# pqc-rev2.net
KiCad netlist of a schematic drawn in EAGLE
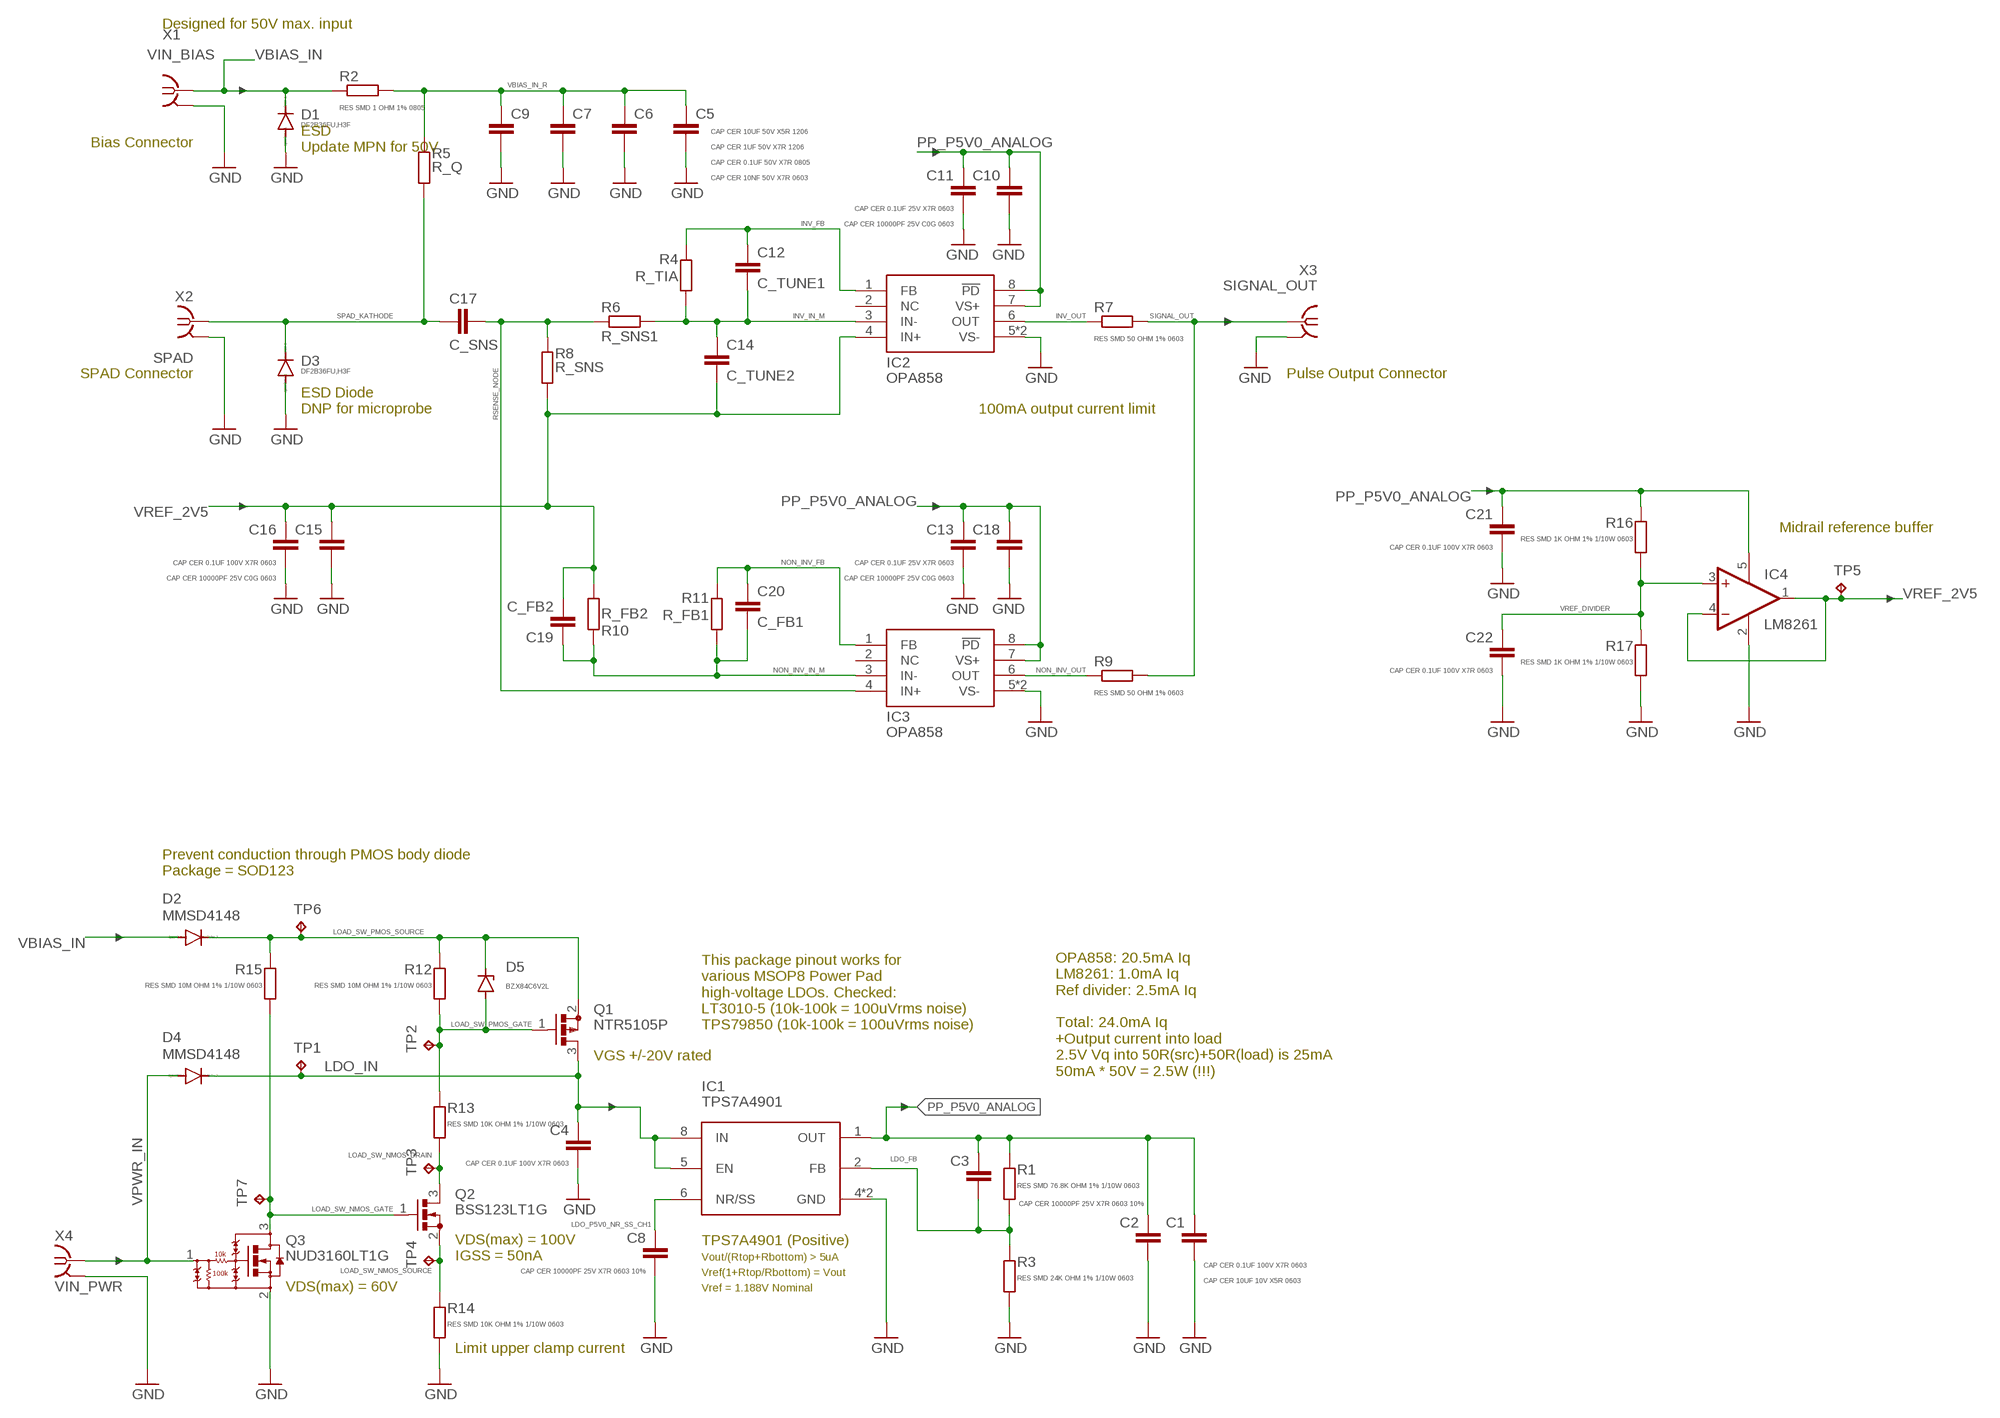
[diagram p0: schematic, sheet 1]

(export (version "E")
  (design (tool "Eeschema 10.0.6"))
  (components
    (comp (ref "C1")
      (value "CAP CER 10UF 10V X5R 0603")
      (footprint "eagle-import:C0603")
      (libsource (lib "eagle-import") (part "rcl-modified-footprints_C-EUC0603"))
    )
    (comp (ref "C2")
      (value "CAP CER 0.1UF 100V X7R 0603")
      (footprint "eagle-import:C0603")
      (libsource (lib "eagle-import") (part "rcl-modified-footprints_C-EUC0603"))
    )
    (comp (ref "C3")
      (value "CAP CER 10000PF 25V X7R 0603 10%")
      (footprint "eagle-import:C0603")
      (libsource (lib "eagle-import") (part "rcl-modified-footprints_C-EUC0603"))
    )
    (comp (ref "C4")
      (value "CAP CER 0.1UF 100V X7R 0603")
      (footprint "eagle-import:C0603")
      (libsource (lib "eagle-import") (part "rcl-modified-footprints_C-EUC0603"))
    )
    (comp (ref "C5")
      (value "CAP CER 10UF 50V X5R 1206")
      (footprint "eagle-import:C1206")
      (libsource (lib "eagle-import") (part "C-EUC1206"))
    )
    (comp (ref "C6")
      (value "CAP CER 1UF 50V X7R 1206")
      (footprint "eagle-import:C1206")
      (libsource (lib "eagle-import") (part "C-EUC1206"))
    )
    (comp (ref "C7")
      (value "CAP CER 0.1UF 50V X7R 0805")
      (footprint "eagle-import:C0805")
      (libsource (lib "eagle-import") (part "C-EUC0805"))
    )
    (comp (ref "C8")
      (value "CAP CER 10000PF 25V X7R 0603 10%")
      (footprint "eagle-import:C0603")
      (libsource (lib "eagle-import") (part "rcl-modified-footprints_C-EUC0603"))
    )
    (comp (ref "C9")
      (value "CAP CER 10NF 50V X7R 0603")
      (footprint "eagle-import:C0603")
      (libsource (lib "eagle-import") (part "rcl-modified-footprints_C-EUC0603"))
    )
    (comp (ref "C10")
      (value "CAP CER 10000PF 25V C0G 0603")
      (footprint "eagle-import:C0603")
      (libsource (lib "eagle-import") (part "rcl-modified-footprints_C-EUC0603"))
    )
    (comp (ref "C11")
      (value "CAP CER 0.1UF 25V X7R 0603")
      (footprint "eagle-import:C0603")
      (libsource (lib "eagle-import") (part "rcl-modified-footprints_C-EUC0603"))
    )
    (comp (ref "C12")
      (value "C_TUNE1")
      (footprint "eagle-import:C0402")
      (libsource (lib "eagle-import") (part "rcl-modified-footprints_C-EUC0402"))
    )
    (comp (ref "C13")
      (value "CAP CER 0.1UF 25V X7R 0603")
      (footprint "eagle-import:C0603")
      (libsource (lib "eagle-import") (part "rcl-modified-footprints_C-EUC0603"))
    )
    (comp (ref "C14")
      (value "C_TUNE2")
      (footprint "eagle-import:C0402")
      (libsource (lib "eagle-import") (part "rcl-modified-footprints_C-EUC0402"))
    )
    (comp (ref "C15")
      (value "CAP CER 10000PF 25V C0G 0603")
      (footprint "eagle-import:C0603")
      (libsource (lib "eagle-import") (part "rcl-modified-footprints_C-EUC0603"))
    )
    (comp (ref "C16")
      (value "CAP CER 0.1UF 100V X7R 0603")
      (footprint "eagle-import:C0603")
      (libsource (lib "eagle-import") (part "rcl-modified-footprints_C-EUC0603"))
    )
    (comp (ref "C17")
      (value "C_SNS")
      (footprint "eagle-import:C0603")
      (libsource (lib "eagle-import") (part "rcl-modified-footprints_C-EUC0603"))
    )
    (comp (ref "C18")
      (value "CAP CER 10000PF 25V C0G 0603")
      (footprint "eagle-import:C0603")
      (libsource (lib "eagle-import") (part "rcl-modified-footprints_C-EUC0603"))
    )
    (comp (ref "C19")
      (value "C_FB2")
      (footprint "eagle-import:C0402")
      (libsource (lib "eagle-import") (part "rcl-modified-footprints_C-EUC0402"))
    )
    (comp (ref "C20")
      (value "C_FB1")
      (footprint "eagle-import:C0402")
      (libsource (lib "eagle-import") (part "rcl-modified-footprints_C-EUC0402"))
    )
    (comp (ref "C21")
      (value "CAP CER 0.1UF 100V X7R 0603")
      (footprint "eagle-import:C0603")
      (libsource (lib "eagle-import") (part "rcl-modified-footprints_C-EUC0603"))
    )
    (comp (ref "C22")
      (value "CAP CER 0.1UF 100V X7R 0603")
      (footprint "eagle-import:C0603")
      (libsource (lib "eagle-import") (part "rcl-modified-footprints_C-EUC0603"))
    )
    (comp (ref "D1")
      (value "DF2B36FU,H3F")
      (footprint "eagle-import:SOD323-W")
      (libsource (lib "eagle-import") (part "DIODE-SOD323-W"))
    )
    (comp (ref "D2")
      (value "MMSD4148")
      (footprint "eagle-import:SOD123")
      (libsource (lib "eagle-import") (part "DIODE-SOD123"))
    )
    (comp (ref "D3")
      (value "DF2B36FU,H3F")
      (footprint "eagle-import:SOD323-W")
      (libsource (lib "eagle-import") (part "DIODE-SOD323-W"))
    )
    (comp (ref "D4")
      (value "MMSD4148")
      (footprint "eagle-import:SOD123")
      (libsource (lib "eagle-import") (part "DIODE-SOD123"))
    )
    (comp (ref "D5")
      (value "BZX84C6V2L")
      (footprint "eagle-import:SOT23")
      (libsource (lib "eagle-import") (part "ZENER-DIODESOT23"))
    )
    (comp (ref "IC1")
      (value "TPS7A4901")
      (footprint "eagle-import:MSOP-8_POWER_PAD")
      (libsource (lib "eagle-import") (part "TPS7A"))
    )
    (comp (ref "IC2")
      (value "OPA858")
      (footprint "eagle-import:WSON8")
      (libsource (lib "eagle-import") (part "OPA858"))
    )
    (comp (ref "IC3")
      (value "OPA858")
      (footprint "eagle-import:WSON8")
      (libsource (lib "eagle-import") (part "OPA858"))
    )
    (comp (ref "IC4")
      (value "LM8261")
      (footprint "eagle-import:SOT23-5")
      (libsource (lib "eagle-import") (part "LM8261"))
    )
    (comp (ref "Q1")
      (value "NTR5105P")
      (footprint "eagle-import:SOT23C")
      (libsource (lib "eagle-import") (part "PMOS_GENERIC_SOT23-3"))
    )
    (comp (ref "Q2")
      (value "BSS123LT1G")
      (footprint "eagle-import:SOT23C")
      (libsource (lib "eagle-import") (part "NMOS_GENERIC"))
    )
    (comp (ref "Q3")
      (value "NUD3160LT1G")
      (footprint "eagle-import:SOT23C")
      (libsource (lib "eagle-import") (part "NUD3160LT1G"))
    )
    (comp (ref "R1")
      (value "RES SMD 76.8K OHM 1% 1/10W 0603")
      (footprint "eagle-import:R0603")
      (libsource (lib "eagle-import") (part "R-EU_R0603"))
    )
    (comp (ref "R2")
      (value "RES SMD 1 OHM 1% 0805")
      (footprint "eagle-import:R0805")
      (libsource (lib "eagle-import") (part "rcl_334_R-EU_R0805"))
    )
    (comp (ref "R3")
      (value "RES SMD 24K OHM 1% 1/10W 0603")
      (footprint "eagle-import:R0603")
      (libsource (lib "eagle-import") (part "R-EU_R0603"))
    )
    (comp (ref "R4")
      (value "R_TIA")
      (footprint "eagle-import:R0402")
      (libsource (lib "eagle-import") (part "R-EU_R0402"))
    )
    (comp (ref "R5")
      (value "R_Q")
      (footprint "eagle-import:R0805")
      (libsource (lib "eagle-import") (part "rcl_334_R-EU_R0805"))
    )
    (comp (ref "R6")
      (value "R_SNS1")
      (footprint "eagle-import:R0402")
      (libsource (lib "eagle-import") (part "R-EU_R0402"))
    )
    (comp (ref "R7")
      (value "RES SMD 50 OHM 1% 0603")
      (footprint "eagle-import:R0603")
      (libsource (lib "eagle-import") (part "R-EU_R0603"))
    )
    (comp (ref "R8")
      (value "R_SNS")
      (footprint "eagle-import:R0402")
      (libsource (lib "eagle-import") (part "R-EU_R0402"))
    )
    (comp (ref "R9")
      (value "RES SMD 50 OHM 1% 0603")
      (footprint "eagle-import:R0603")
      (libsource (lib "eagle-import") (part "R-EU_R0603"))
    )
    (comp (ref "R10")
      (value "R_FB2")
      (footprint "eagle-import:R0402")
      (libsource (lib "eagle-import") (part "R-EU_R0402"))
    )
    (comp (ref "R11")
      (value "R_FB1")
      (footprint "eagle-import:R0402")
      (libsource (lib "eagle-import") (part "R-EU_R0402"))
    )
    (comp (ref "R12")
      (value "RES SMD 10M OHM 1% 1/10W 0603")
      (footprint "eagle-import:R0603")
      (libsource (lib "eagle-import") (part "R-EU_R0603"))
    )
    (comp (ref "R13")
      (value "RES SMD 10K OHM 1% 1/10W 0603")
      (footprint "eagle-import:R0603")
      (libsource (lib "eagle-import") (part "R-EU_R0603"))
    )
    (comp (ref "R14")
      (value "RES SMD 10K OHM 1% 1/10W 0603")
      (footprint "eagle-import:R0603")
      (libsource (lib "eagle-import") (part "R-EU_R0603"))
    )
    (comp (ref "R15")
      (value "RES SMD 10M OHM 1% 1/10W 0603")
      (footprint "eagle-import:R0603")
      (libsource (lib "eagle-import") (part "R-EU_R0603"))
    )
    (comp (ref "R16")
      (value "RES SMD 1K OHM 1% 1/10W 0603")
      (footprint "eagle-import:R0603")
      (libsource (lib "eagle-import") (part "R-EU_R0603"))
    )
    (comp (ref "R17")
      (value "RES SMD 1K OHM 1% 1/10W 0603")
      (footprint "eagle-import:R0603")
      (libsource (lib "eagle-import") (part "R-EU_R0603"))
    )
    (comp (ref "TP1")
      (value "TPTP10R")
      (footprint "eagle-import:TP10R")
      (libsource (lib "eagle-import") (part "TPTP10R"))
    )
    (comp (ref "TP2")
      (value "TPTP10R")
      (footprint "eagle-import:TP10R")
      (libsource (lib "eagle-import") (part "TPTP10R"))
    )
    (comp (ref "TP3")
      (value "TPTP10R")
      (footprint "eagle-import:TP10R")
      (libsource (lib "eagle-import") (part "TPTP10R"))
    )
    (comp (ref "TP4")
      (value "TPTP10R")
      (footprint "eagle-import:TP10R")
      (libsource (lib "eagle-import") (part "TPTP10R"))
    )
    (comp (ref "TP5")
      (value "TPTP10R")
      (footprint "eagle-import:TP10R")
      (libsource (lib "eagle-import") (part "TPTP10R"))
    )
    (comp (ref "TP6")
      (value "TPTP10R")
      (footprint "eagle-import:TP10R")
      (libsource (lib "eagle-import") (part "TPTP10R"))
    )
    (comp (ref "TP7")
      (value "TPB1,27")
      (footprint "eagle-import:B1,27")
      (libsource (lib "eagle-import") (part "TPB1,27"))
    )
    (comp (ref "X1")
      (value "VIN_BIAS")
      (footprint "eagle-import:MMCX-J-P-X-ST-EM1-MKT")
      (fields (field (name "MF") "Samtec Inc.") (field (name "MPN") "MMCX-J-P-X-ST-EM1-MKT"))
      (libsource (lib "eagle-import") (part "COAX"))
    )
    (comp (ref "X2")
      (value "SPAD")
      (footprint "eagle-import:J502-ND-142-0701-881_886")
      (fields (field (name "MF") "JOHNSON COMPONENTS") (field (name "MPN") "142-0701-881"))
      (libsource (lib "eagle-import") (part "SMA-142-0701-881/886"))
    )
    (comp (ref "X3")
      (value "SIGNAL_OUT")
      (footprint "eagle-import:MMCX-J-P-X-ST-EM1-MKT")
      (fields (field (name "MF") "Samtec Inc.") (field (name "MPN") "MMCX-J-P-X-ST-EM1-MKT"))
      (libsource (lib "eagle-import") (part "COAX"))
    )
    (comp (ref "X4")
      (value "VIN_PWR")
      (footprint "eagle-import:MMCX-J-P-X-ST-EM1-MKT")
      (fields (field (name "MF") "Samtec Inc.") (field (name "MPN") "MMCX-J-P-X-ST-EM1-MKT"))
      (libsource (lib "eagle-import") (part "COAX"))
    )
  )
  (nets
    (net (code "1") (name "/INV_FB") (class "Default")
      (node (ref "C12") (pin "1") (pinfunction "1_1") (pintype "passive"))
      (node (ref "IC2") (pin "1") (pinfunction "FB_1") (pintype "bidirectional"))
      (node (ref "R4") (pin "1") (pinfunction "1_1") (pintype "passive"))
    )
    (net (code "2") (name "/INV_IN_M") (class "Default")
      (node (ref "C12") (pin "2") (pinfunction "2_2") (pintype "passive"))
      (node (ref "C14") (pin "1") (pinfunction "1_1") (pintype "passive"))
      (node (ref "IC2") (pin "3") (pinfunction "IN-_3") (pintype "bidirectional"))
      (node (ref "R4") (pin "2") (pinfunction "2_2") (pintype "passive"))
      (node (ref "R6") (pin "1") (pinfunction "1_1") (pintype "passive"))
    )
    (net (code "3") (name "/INV_OUT") (class "Default")
      (node (ref "IC2") (pin "6") (pinfunction "OUT_6") (pintype "bidirectional"))
      (node (ref "R7") (pin "2") (pinfunction "2_2") (pintype "passive"))
    )
    (net (code "4") (name "/LDO_FB") (class "Default")
      (node (ref "C3") (pin "2") (pinfunction "2_2") (pintype "passive"))
      (node (ref "IC1") (pin "2") (pinfunction "FB_2") (pintype "bidirectional"))
      (node (ref "R1") (pin "1") (pinfunction "1_1") (pintype "passive"))
      (node (ref "R3") (pin "1") (pinfunction "1_1") (pintype "passive"))
    )
    (net (code "5") (name "/LDO_IN") (class "Default")
      (node (ref "C4") (pin "1") (pinfunction "1_1") (pintype "passive"))
      (node (ref "D4") (pin "C") (pinfunction "C_C") (pintype "passive"))
      (node (ref "IC1") (pin "5") (pinfunction "EN_5") (pintype "bidirectional"))
      (node (ref "IC1") (pin "8") (pinfunction "IN_8") (pintype "bidirectional"))
      (node (ref "Q1") (pin "3") (pinfunction "D_3") (pintype "passive"))
      (node (ref "TP1") (pin "TP") (pinfunction "TP_TP") (pintype "input"))
    )
    (net (code "6") (name "/LDO_P5V0_NR_SS_CH1") (class "Default")
      (node (ref "C8") (pin "1") (pinfunction "1_1") (pintype "passive"))
      (node (ref "IC1") (pin "6") (pinfunction "NR/SS_6") (pintype "bidirectional"))
    )
    (net (code "7") (name "/LOAD_SW_NMOS_DRAIN") (class "Default")
      (node (ref "Q2") (pin "3") (pinfunction "D_3") (pintype "passive"))
      (node (ref "R13") (pin "1") (pinfunction "1_1") (pintype "passive"))
      (node (ref "TP3") (pin "TP") (pinfunction "TP_TP") (pintype "input"))
    )
    (net (code "8") (name "/LOAD_SW_NMOS_GATE") (class "Default")
      (node (ref "Q2") (pin "1") (pinfunction "G_1") (pintype "passive"))
      (node (ref "Q3") (pin "3") (pinfunction "D_3") (pintype "passive"))
      (node (ref "R15") (pin "1") (pinfunction "1_1") (pintype "passive"))
      (node (ref "TP7") (pin "TP") (pinfunction "TP_TP") (pintype "input"))
    )
    (net (code "9") (name "/LOAD_SW_NMOS_SOURCE") (class "Default")
      (node (ref "Q2") (pin "2") (pinfunction "S_2") (pintype "passive"))
      (node (ref "R14") (pin "2") (pinfunction "2_2") (pintype "passive"))
      (node (ref "TP4") (pin "TP") (pinfunction "TP_TP") (pintype "input"))
    )
    (net (code "10") (name "/LOAD_SW_PMOS_GATE") (class "Default")
      (node (ref "D5") (pin "1") (pinfunction "A_1") (pintype "passive"))
      (node (ref "Q1") (pin "1") (pinfunction "G_1") (pintype "passive"))
      (node (ref "R12") (pin "1") (pinfunction "1_1") (pintype "passive"))
      (node (ref "R13") (pin "2") (pinfunction "2_2") (pintype "passive"))
      (node (ref "TP2") (pin "TP") (pinfunction "TP_TP") (pintype "input"))
    )
    (net (code "11") (name "/LOAD_SW_PMOS_SOURCE") (class "Default")
      (node (ref "D2") (pin "C") (pinfunction "C_C") (pintype "passive"))
      (node (ref "D5") (pin "3") (pinfunction "C_3") (pintype "passive"))
      (node (ref "Q1") (pin "2") (pinfunction "S_2") (pintype "passive"))
      (node (ref "R12") (pin "2") (pinfunction "2_2") (pintype "passive"))
      (node (ref "R15") (pin "2") (pinfunction "2_2") (pintype "passive"))
      (node (ref "TP6") (pin "TP") (pinfunction "TP_TP") (pintype "input"))
    )
    (net (code "12") (name "/NON_INV_FB") (class "Default")
      (node (ref "C20") (pin "1") (pinfunction "1_1") (pintype "passive"))
      (node (ref "IC3") (pin "1") (pinfunction "FB_1") (pintype "bidirectional"))
      (node (ref "R11") (pin "1") (pinfunction "1_1") (pintype "passive"))
    )
    (net (code "13") (name "/NON_INV_IN_M") (class "Default")
      (node (ref "C19") (pin "1") (pinfunction "1_1") (pintype "passive"))
      (node (ref "C20") (pin "2") (pinfunction "2_2") (pintype "passive"))
      (node (ref "IC3") (pin "3") (pinfunction "IN-_3") (pintype "bidirectional"))
      (node (ref "R10") (pin "1") (pinfunction "1_1") (pintype "passive"))
      (node (ref "R11") (pin "2") (pinfunction "2_2") (pintype "passive"))
    )
    (net (code "14") (name "/NON_INV_OUT") (class "Default")
      (node (ref "IC3") (pin "6") (pinfunction "OUT_6") (pintype "bidirectional"))
      (node (ref "R9") (pin "2") (pinfunction "2_2") (pintype "passive"))
    )
    (net (code "15") (name "/RSENSE_NODE") (class "Default")
      (node (ref "C17") (pin "2") (pinfunction "2_2") (pintype "passive"))
      (node (ref "IC3") (pin "4") (pinfunction "IN+_4") (pintype "bidirectional"))
      (node (ref "R6") (pin "2") (pinfunction "2_2") (pintype "passive"))
      (node (ref "R8") (pin "2") (pinfunction "2_2") (pintype "passive"))
    )
    (net (code "16") (name "/SIGNAL_OUT") (class "Default")
      (node (ref "R7") (pin "1") (pinfunction "1_1") (pintype "passive"))
      (node (ref "R9") (pin "1") (pinfunction "1_1") (pintype "passive"))
      (node (ref "X3") (pin "1") (pinfunction "1_1") (pintype "passive"))
    )
    (net (code "17") (name "/SPAD_KATHODE") (class "Default")
      (node (ref "C17") (pin "1") (pinfunction "1_1") (pintype "passive"))
      (node (ref "D3") (pin "C") (pinfunction "C_C") (pintype "passive"))
      (node (ref "R5") (pin "1") (pinfunction "1_1") (pintype "passive"))
      (node (ref "X2") (pin "1") (pinfunction "1_1") (pintype "passive"))
    )
    (net (code "18") (name "/VBIAS_IN") (class "Default")
      (node (ref "D1") (pin "C") (pinfunction "C_C") (pintype "passive"))
      (node (ref "D2") (pin "A") (pinfunction "A_A") (pintype "passive"))
      (node (ref "R2") (pin "2") (pinfunction "2_2") (pintype "passive"))
      (node (ref "X1") (pin "1") (pinfunction "1_1") (pintype "passive"))
    )
    (net (code "19") (name "/VBIAS_IN_R") (class "Default")
      (node (ref "C5") (pin "1") (pinfunction "1_1") (pintype "passive"))
      (node (ref "C6") (pin "1") (pinfunction "1_1") (pintype "passive"))
      (node (ref "C7") (pin "1") (pinfunction "1_1") (pintype "passive"))
      (node (ref "C9") (pin "1") (pinfunction "1_1") (pintype "passive"))
      (node (ref "R2") (pin "1") (pinfunction "1_1") (pintype "passive"))
      (node (ref "R5") (pin "2") (pinfunction "2_2") (pintype "passive"))
    )
    (net (code "20") (name "/VPWR_IN") (class "Default")
      (node (ref "D4") (pin "A") (pinfunction "A_A") (pintype "passive"))
      (node (ref "Q3") (pin "1") (pinfunction "G_1") (pintype "passive"))
      (node (ref "X4") (pin "1") (pinfunction "1_1") (pintype "passive"))
    )
    (net (code "21") (name "/VREF_2V5") (class "Default")
      (node (ref "C14") (pin "2") (pinfunction "2_2") (pintype "passive"))
      (node (ref "C15") (pin "1") (pinfunction "1_1") (pintype "passive"))
      (node (ref "C16") (pin "1") (pinfunction "1_1") (pintype "passive"))
      (node (ref "C19") (pin "2") (pinfunction "2_2") (pintype "passive"))
      (node (ref "IC2") (pin "4") (pinfunction "IN+_4") (pintype "bidirectional"))
      (node (ref "IC4") (pin "1") (pinfunction "OUT_1") (pintype "output"))
      (node (ref "IC4") (pin "4") (pinfunction "-IN_4") (pintype "input"))
      (node (ref "R10") (pin "2") (pinfunction "2_2") (pintype "passive"))
      (node (ref "R8") (pin "1") (pinfunction "1_1") (pintype "passive"))
      (node (ref "TP5") (pin "TP") (pinfunction "TP_TP") (pintype "input"))
    )
    (net (code "22") (name "/VREF_DIVIDER") (class "Default")
      (node (ref "C22") (pin "1") (pinfunction "1_1") (pintype "passive"))
      (node (ref "IC4") (pin "3") (pinfunction "+IN_3") (pintype "input"))
      (node (ref "R16") (pin "1") (pinfunction "1_1") (pintype "passive"))
      (node (ref "R17") (pin "2") (pinfunction "2_2") (pintype "passive"))
    )
    (net (code "23") (name "GND") (class "Default")
      (node (ref "C1") (pin "2") (pinfunction "2_2") (pintype "passive"))
      (node (ref "C10") (pin "2") (pinfunction "2_2") (pintype "passive"))
      (node (ref "C11") (pin "2") (pinfunction "2_2") (pintype "passive"))
      (node (ref "C13") (pin "2") (pinfunction "2_2") (pintype "passive"))
      (node (ref "C15") (pin "2") (pinfunction "2_2") (pintype "passive"))
      (node (ref "C16") (pin "2") (pinfunction "2_2") (pintype "passive"))
      (node (ref "C18") (pin "2") (pinfunction "2_2") (pintype "passive"))
      (node (ref "C2") (pin "2") (pinfunction "2_2") (pintype "passive"))
      (node (ref "C21") (pin "2") (pinfunction "2_2") (pintype "passive"))
      (node (ref "C22") (pin "2") (pinfunction "2_2") (pintype "passive"))
      (node (ref "C4") (pin "2") (pinfunction "2_2") (pintype "passive"))
      (node (ref "C5") (pin "2") (pinfunction "2_2") (pintype "passive"))
      (node (ref "C6") (pin "2") (pinfunction "2_2") (pintype "passive"))
      (node (ref "C7") (pin "2") (pinfunction "2_2") (pintype "passive"))
      (node (ref "C8") (pin "2") (pinfunction "2_2") (pintype "passive"))
      (node (ref "C9") (pin "2") (pinfunction "2_2") (pintype "passive"))
      (node (ref "D1") (pin "A") (pinfunction "A_A") (pintype "passive"))
      (node (ref "D3") (pin "A") (pinfunction "A_A") (pintype "passive"))
      (node (ref "IC1") (pin "4") (pinfunction "GND_4") (pintype "bidirectional"))
      (node (ref "IC1") (pin "PAD") (pinfunction "GND_PAD") (pintype "bidirectional"))
      (node (ref "IC2") (pin "5") (pinfunction "VS-_5") (pintype "bidirectional"))
      (node (ref "IC2") (pin "PAD") (pinfunction "VS-_PAD") (pintype "bidirectional"))
      (node (ref "IC3") (pin "5") (pinfunction "VS-_5") (pintype "bidirectional"))
      (node (ref "IC3") (pin "PAD") (pinfunction "VS-_PAD") (pintype "bidirectional"))
      (node (ref "IC4") (pin "2") (pinfunction "V-_2") (pintype "power_in"))
      (node (ref "Q3") (pin "2") (pinfunction "S_2") (pintype "passive"))
      (node (ref "R14") (pin "1") (pinfunction "1_1") (pintype "passive"))
      (node (ref "R17") (pin "1") (pinfunction "1_1") (pintype "passive"))
      (node (ref "R3") (pin "2") (pinfunction "2_2") (pintype "passive"))
      (node (ref "X1") (pin "2@1") (pinfunction "GND_2@1") (pintype "power_in"))
      (node (ref "X2") (pin "G@1") (pinfunction "GND_G@1") (pintype "power_in"))
      (node (ref "X3") (pin "2@1") (pinfunction "GND_2@1") (pintype "power_in"))
      (node (ref "X4") (pin "2@1") (pinfunction "GND_2@1") (pintype "power_in"))
    )
    (net (code "24") (name "PP_P5V0_ANALOG") (class "Default")
      (node (ref "C1") (pin "1") (pinfunction "1_1") (pintype "passive"))
      (node (ref "C10") (pin "1") (pinfunction "1_1") (pintype "passive"))
      (node (ref "C11") (pin "1") (pinfunction "1_1") (pintype "passive"))
      (node (ref "C13") (pin "1") (pinfunction "1_1") (pintype "passive"))
      (node (ref "C18") (pin "1") (pinfunction "1_1") (pintype "passive"))
      (node (ref "C2") (pin "1") (pinfunction "1_1") (pintype "passive"))
      (node (ref "C21") (pin "1") (pinfunction "1_1") (pintype "passive"))
      (node (ref "C3") (pin "1") (pinfunction "1_1") (pintype "passive"))
      (node (ref "IC1") (pin "1") (pinfunction "OUT_1") (pintype "bidirectional"))
      (node (ref "IC2") (pin "7") (pinfunction "VS+_7") (pintype "bidirectional"))
      (node (ref "IC2") (pin "8") (pinfunction "~{PD}_8") (pintype "bidirectional"))
      (node (ref "IC3") (pin "7") (pinfunction "VS+_7") (pintype "bidirectional"))
      (node (ref "IC3") (pin "8") (pinfunction "~{PD}_8") (pintype "bidirectional"))
      (node (ref "IC4") (pin "5") (pinfunction "V+_5") (pintype "power_in"))
      (node (ref "R1") (pin "2") (pinfunction "2_2") (pintype "passive"))
      (node (ref "R16") (pin "2") (pinfunction "2_2") (pintype "passive"))
    )
    (net (code "25") (name "unconnected-(IC2-NC-Pad2)") (class "Default")
      (node (ref "IC2") (pin "2") (pinfunction "NC_2") (pintype "bidirectional"))
    )
    (net (code "26") (name "unconnected-(IC3-NC-Pad2)") (class "Default")
      (node (ref "IC3") (pin "2") (pinfunction "NC_2") (pintype "bidirectional"))
    )
  )
)
